# MCU_IO.net
KiCad netlist of a schematic drawn in Altium Designer
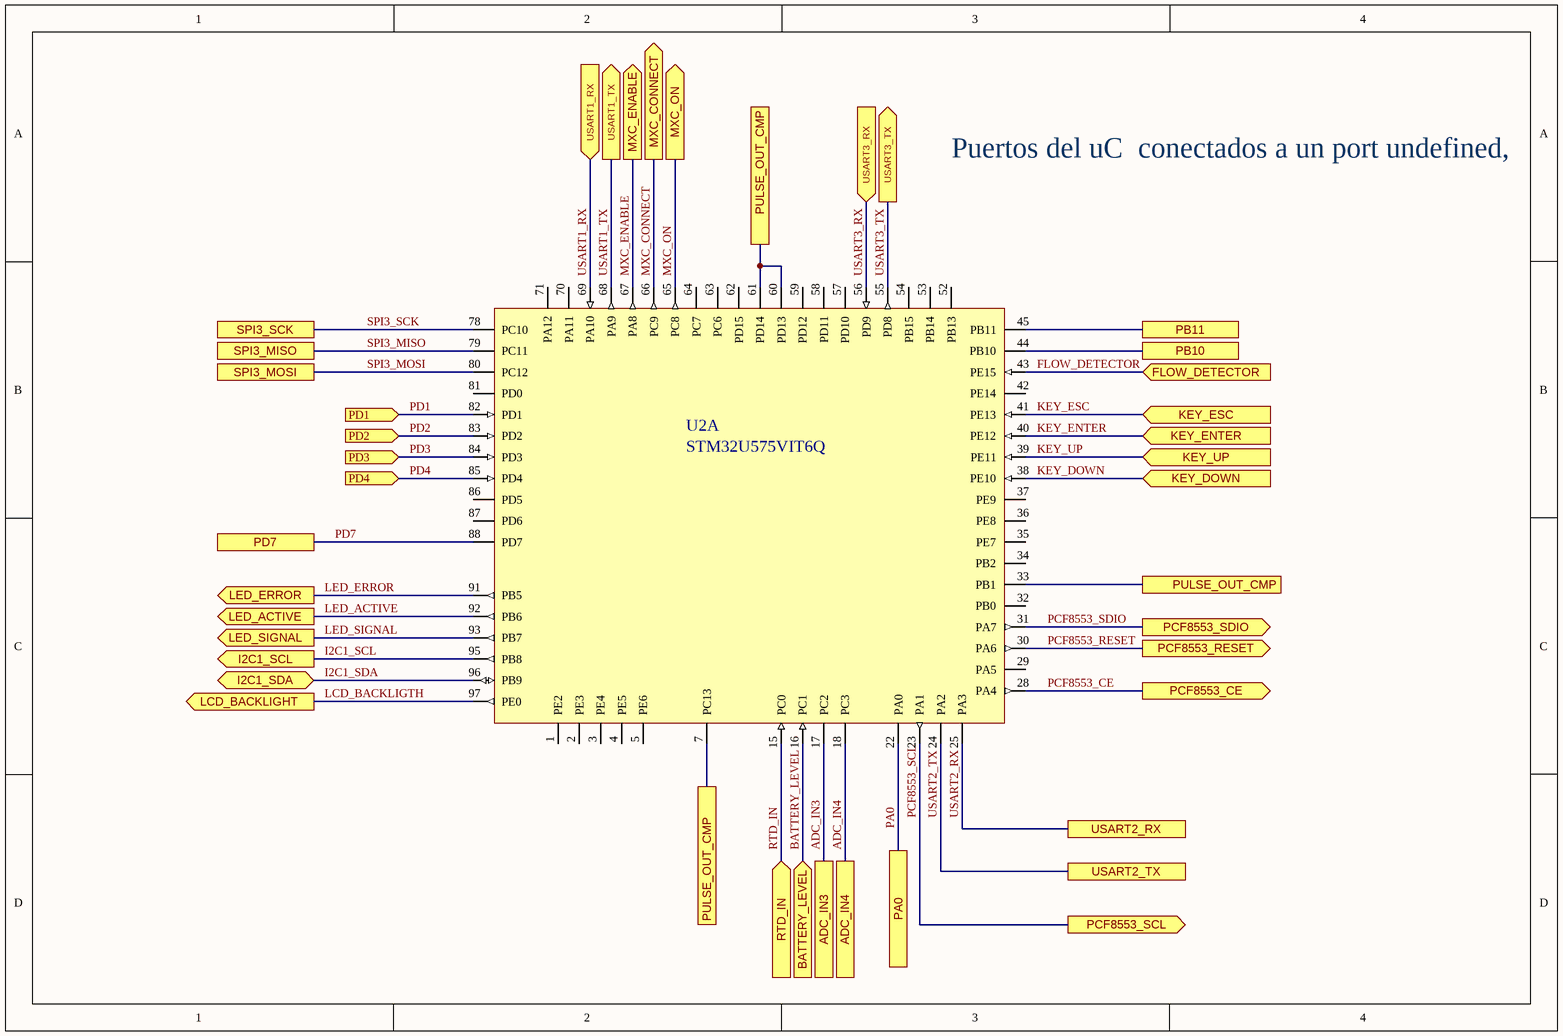
[diagram p0: MCU_IO.SchDoc]

(export (version "E")
  (design (tool "Eeschema 10.0.6"))
  (components
    (comp (ref "U2")
      (value "STM32U575VIT6Q")
      (footprint "STM32U575VI")
      (fields (field (name "MANUFACTURER") "ST"))
      (libsource (lib "Microcontroladores") (part "STM32U575VI_1"))
    )
  )
  (nets
    (net (code "1") (name "/ADC_IN3") (class "Default")
      (node (ref "U2") (pin "17") (pinfunction "PC2_17") (pintype "tri_state"))
    )
    (net (code "2") (name "/ADC_IN4") (class "Default")
      (node (ref "U2") (pin "18") (pinfunction "PC3_18") (pintype "tri_state"))
    )
    (net (code "3") (name "/BATTERY_LEVEL") (class "Default")
      (node (ref "U2") (pin "16") (pinfunction "PC1_16") (pintype "input"))
    )
    (net (code "4") (name "/FLOW_DETECTOR") (class "Default")
      (node (ref "U2") (pin "43") (pinfunction "PE15_43") (pintype "input"))
    )
    (net (code "5") (name "/I2C1_SCL") (class "Default")
      (node (ref "U2") (pin "95") (pinfunction "PB8_95") (pintype "output"))
    )
    (net (code "6") (name "/I2C1_SDA") (class "Default")
      (node (ref "U2") (pin "96") (pinfunction "PB9_96") (pintype "bidirectional"))
    )
    (net (code "7") (name "/KEY_DOWN") (class "Default")
      (node (ref "U2") (pin "38") (pinfunction "PE10_38") (pintype "input"))
    )
    (net (code "8") (name "/KEY_ENTER") (class "Default")
      (node (ref "U2") (pin "40") (pinfunction "PE12_40") (pintype "input"))
    )
    (net (code "9") (name "/KEY_ESC") (class "Default")
      (node (ref "U2") (pin "41") (pinfunction "PE13_41") (pintype "input"))
    )
    (net (code "10") (name "/KEY_UP") (class "Default")
      (node (ref "U2") (pin "39") (pinfunction "PE11_39") (pintype "input"))
    )
    (net (code "11") (name "/LCD_BACKLIGTH") (class "Default")
      (node (ref "U2") (pin "97") (pinfunction "PE0_97") (pintype "output"))
    )
    (net (code "12") (name "/LED_ACTIVE") (class "Default")
      (node (ref "U2") (pin "92") (pinfunction "PB6_92") (pintype "output"))
    )
    (net (code "13") (name "/LED_ERROR") (class "Default")
      (node (ref "U2") (pin "91") (pinfunction "PB5_91") (pintype "output"))
    )
    (net (code "14") (name "/LED_SIGNAL") (class "Default")
      (node (ref "U2") (pin "93") (pinfunction "PB7_93") (pintype "output"))
    )
    (net (code "15") (name "/MXC_CONNECT") (class "Default")
      (node (ref "U2") (pin "66") (pinfunction "PC9_66") (pintype "output"))
    )
    (net (code "16") (name "/MXC_ENABLE") (class "Default")
      (node (ref "U2") (pin "67") (pinfunction "PA8_67") (pintype "output"))
    )
    (net (code "17") (name "/MXC_ON") (class "Default")
      (node (ref "U2") (pin "65") (pinfunction "PC8_65") (pintype "output"))
    )
    (net (code "18") (name "/PA0") (class "Default")
      (node (ref "U2") (pin "22") (pinfunction "PA0_22") (pintype "tri_state"))
    )
    (net (code "19") (name "/PB10") (class "Default")
      (node (ref "U2") (pin "44") (pinfunction "PB10_44") (pintype "tri_state"))
    )
    (net (code "20") (name "/PB11") (class "Default")
      (node (ref "U2") (pin "45") (pinfunction "PB11_45") (pintype "tri_state"))
    )
    (net (code "21") (name "/PCF8553_CE") (class "Default")
      (node (ref "U2") (pin "28") (pinfunction "PA4_28") (pintype "output"))
    )
    (net (code "22") (name "/PCF8553_RESET") (class "Default")
      (node (ref "U2") (pin "30") (pinfunction "PA6_30") (pintype "output"))
    )
    (net (code "23") (name "/PCF8553_SCL") (class "Default")
      (node (ref "U2") (pin "23") (pinfunction "PA1_23") (pintype "output"))
    )
    (net (code "24") (name "/PCF8553_SDIO") (class "Default")
      (node (ref "U2") (pin "31") (pinfunction "PA7_31") (pintype "output"))
    )
    (net (code "25") (name "/PD1") (class "Default")
      (node (ref "U2") (pin "82") (pinfunction "PD1_82") (pintype "input"))
    )
    (net (code "26") (name "/PD2") (class "Default")
      (node (ref "U2") (pin "83") (pinfunction "PD2_83") (pintype "input"))
    )
    (net (code "27") (name "/PD3") (class "Default")
      (node (ref "U2") (pin "84") (pinfunction "PD3_84") (pintype "input"))
    )
    (net (code "28") (name "/PD4") (class "Default")
      (node (ref "U2") (pin "85") (pinfunction "PD4_85") (pintype "input"))
    )
    (net (code "29") (name "/PD7") (class "Default")
      (node (ref "U2") (pin "88") (pinfunction "PD7_88") (pintype "tri_state"))
    )
    (net (code "30") (name "/PULSE_OUT_CMP") (class "Default")
      (node (ref "U2") (pin "33") (pinfunction "PB1_33") (pintype "tri_state"))
      (node (ref "U2") (pin "60") (pinfunction "PD13_60") (pintype "passive"))
      (node (ref "U2") (pin "61") (pinfunction "PD14_61") (pintype "passive"))
      (node (ref "U2") (pin "7") (pinfunction "PC13_7") (pintype "passive"))
    )
    (net (code "31") (name "/RTD_IN") (class "Default")
      (node (ref "U2") (pin "15") (pinfunction "PC0_15") (pintype "input"))
    )
    (net (code "32") (name "/SPI3_MISO") (class "Default")
      (node (ref "U2") (pin "79") (pinfunction "PC11_79") (pintype "tri_state"))
    )
    (net (code "33") (name "/SPI3_MOSI") (class "Default")
      (node (ref "U2") (pin "80") (pinfunction "PC12_80") (pintype "tri_state"))
    )
    (net (code "34") (name "/SPI3_SCK") (class "Default")
      (node (ref "U2") (pin "78") (pinfunction "PC10_78") (pintype "tri_state"))
    )
    (net (code "35") (name "/USART1_RX") (class "Default")
      (node (ref "U2") (pin "69") (pinfunction "PA10_69") (pintype "input"))
    )
    (net (code "36") (name "/USART1_TX") (class "Default")
      (node (ref "U2") (pin "68") (pinfunction "PA9_68") (pintype "output"))
    )
    (net (code "37") (name "/USART2_RX") (class "Default")
      (node (ref "U2") (pin "25") (pinfunction "PA3_25") (pintype "tri_state"))
    )
    (net (code "38") (name "/USART2_TX") (class "Default")
      (node (ref "U2") (pin "24") (pinfunction "PA2_24") (pintype "tri_state"))
    )
    (net (code "39") (name "/USART3_RX") (class "Default")
      (node (ref "U2") (pin "56") (pinfunction "PD9_56") (pintype "input"))
    )
    (net (code "40") (name "/USART3_TX") (class "Default")
      (node (ref "U2") (pin "55") (pinfunction "PD8_55") (pintype "output"))
    )
    (net (code "41") (name "unconnected-(U2A-PA5-Pad29)") (class "Default")
      (node (ref "U2") (pin "29") (pinfunction "PA5_29") (pintype "tri_state"))
    )
    (net (code "42") (name "unconnected-(U2A-PA11-Pad70)") (class "Default")
      (node (ref "U2") (pin "70") (pinfunction "PA11_70") (pintype "tri_state"))
    )
    (net (code "43") (name "unconnected-(U2A-PA12-Pad71)") (class "Default")
      (node (ref "U2") (pin "71") (pinfunction "PA12_71") (pintype "tri_state"))
    )
    (net (code "44") (name "unconnected-(U2A-PB0-Pad32)") (class "Default")
      (node (ref "U2") (pin "32") (pinfunction "PB0_32") (pintype "tri_state"))
    )
    (net (code "45") (name "unconnected-(U2A-PB2-Pad34)") (class "Default")
      (node (ref "U2") (pin "34") (pinfunction "PB2_34") (pintype "tri_state"))
    )
    (net (code "46") (name "unconnected-(U2A-PB13-Pad52)") (class "Default")
      (node (ref "U2") (pin "52") (pinfunction "PB13_52") (pintype "tri_state"))
    )
    (net (code "47") (name "unconnected-(U2A-PB14-Pad53)") (class "Default")
      (node (ref "U2") (pin "53") (pinfunction "PB14_53") (pintype "tri_state"))
    )
    (net (code "48") (name "unconnected-(U2A-PB15-Pad54)") (class "Default")
      (node (ref "U2") (pin "54") (pinfunction "PB15_54") (pintype "tri_state"))
    )
    (net (code "49") (name "unconnected-(U2A-PC6-Pad63)") (class "Default")
      (node (ref "U2") (pin "63") (pinfunction "PC6_63") (pintype "tri_state"))
    )
    (net (code "50") (name "unconnected-(U2A-PC7-Pad64)") (class "Default")
      (node (ref "U2") (pin "64") (pinfunction "PC7_64") (pintype "tri_state"))
    )
    (net (code "51") (name "unconnected-(U2A-PD0-Pad81)") (class "Default")
      (node (ref "U2") (pin "81") (pinfunction "PD0_81") (pintype "tri_state"))
    )
    (net (code "52") (name "unconnected-(U2A-PD5-Pad86)") (class "Default")
      (node (ref "U2") (pin "86") (pinfunction "PD5_86") (pintype "tri_state"))
    )
    (net (code "53") (name "unconnected-(U2A-PD6-Pad87)") (class "Default")
      (node (ref "U2") (pin "87") (pinfunction "PD6_87") (pintype "tri_state"))
    )
    (net (code "54") (name "unconnected-(U2A-PD10-Pad57)") (class "Default")
      (node (ref "U2") (pin "57") (pinfunction "PD10_57") (pintype "tri_state"))
    )
    (net (code "55") (name "unconnected-(U2A-PD11-Pad58)") (class "Default")
      (node (ref "U2") (pin "58") (pinfunction "PD11_58") (pintype "tri_state"))
    )
    (net (code "56") (name "unconnected-(U2A-PD12-Pad59)") (class "Default")
      (node (ref "U2") (pin "59") (pinfunction "PD12_59") (pintype "tri_state"))
    )
    (net (code "57") (name "unconnected-(U2A-PD15-Pad62)") (class "Default")
      (node (ref "U2") (pin "62") (pinfunction "PD15_62") (pintype "tri_state"))
    )
    (net (code "58") (name "unconnected-(U2A-PE2-Pad1)") (class "Default")
      (node (ref "U2") (pin "1") (pinfunction "PE2_1") (pintype "tri_state"))
    )
    (net (code "59") (name "unconnected-(U2A-PE3-Pad2)") (class "Default")
      (node (ref "U2") (pin "2") (pinfunction "PE3_2") (pintype "tri_state"))
    )
    (net (code "60") (name "unconnected-(U2A-PE4-Pad3)") (class "Default")
      (node (ref "U2") (pin "3") (pinfunction "PE4_3") (pintype "tri_state"))
    )
    (net (code "61") (name "unconnected-(U2A-PE5-Pad4)") (class "Default")
      (node (ref "U2") (pin "4") (pinfunction "PE5_4") (pintype "tri_state"))
    )
    (net (code "62") (name "unconnected-(U2A-PE6-Pad5)") (class "Default")
      (node (ref "U2") (pin "5") (pinfunction "PE6_5") (pintype "tri_state"))
    )
    (net (code "63") (name "unconnected-(U2A-PE7-Pad35)") (class "Default")
      (node (ref "U2") (pin "35") (pinfunction "PE7_35") (pintype "tri_state"))
    )
    (net (code "64") (name "unconnected-(U2A-PE8-Pad36)") (class "Default")
      (node (ref "U2") (pin "36") (pinfunction "PE8_36") (pintype "tri_state"))
    )
    (net (code "65") (name "unconnected-(U2A-PE9-Pad37)") (class "Default")
      (node (ref "U2") (pin "37") (pinfunction "PE9_37") (pintype "tri_state"))
    )
    (net (code "66") (name "unconnected-(U2A-PE14-Pad42)") (class "Default")
      (node (ref "U2") (pin "42") (pinfunction "PE14_42") (pintype "tri_state"))
    )
  )
)
